# project_vostok__tv_b_gone_extended__v2_0.net
KiCad netlist of a schematic drawn in EAGLE
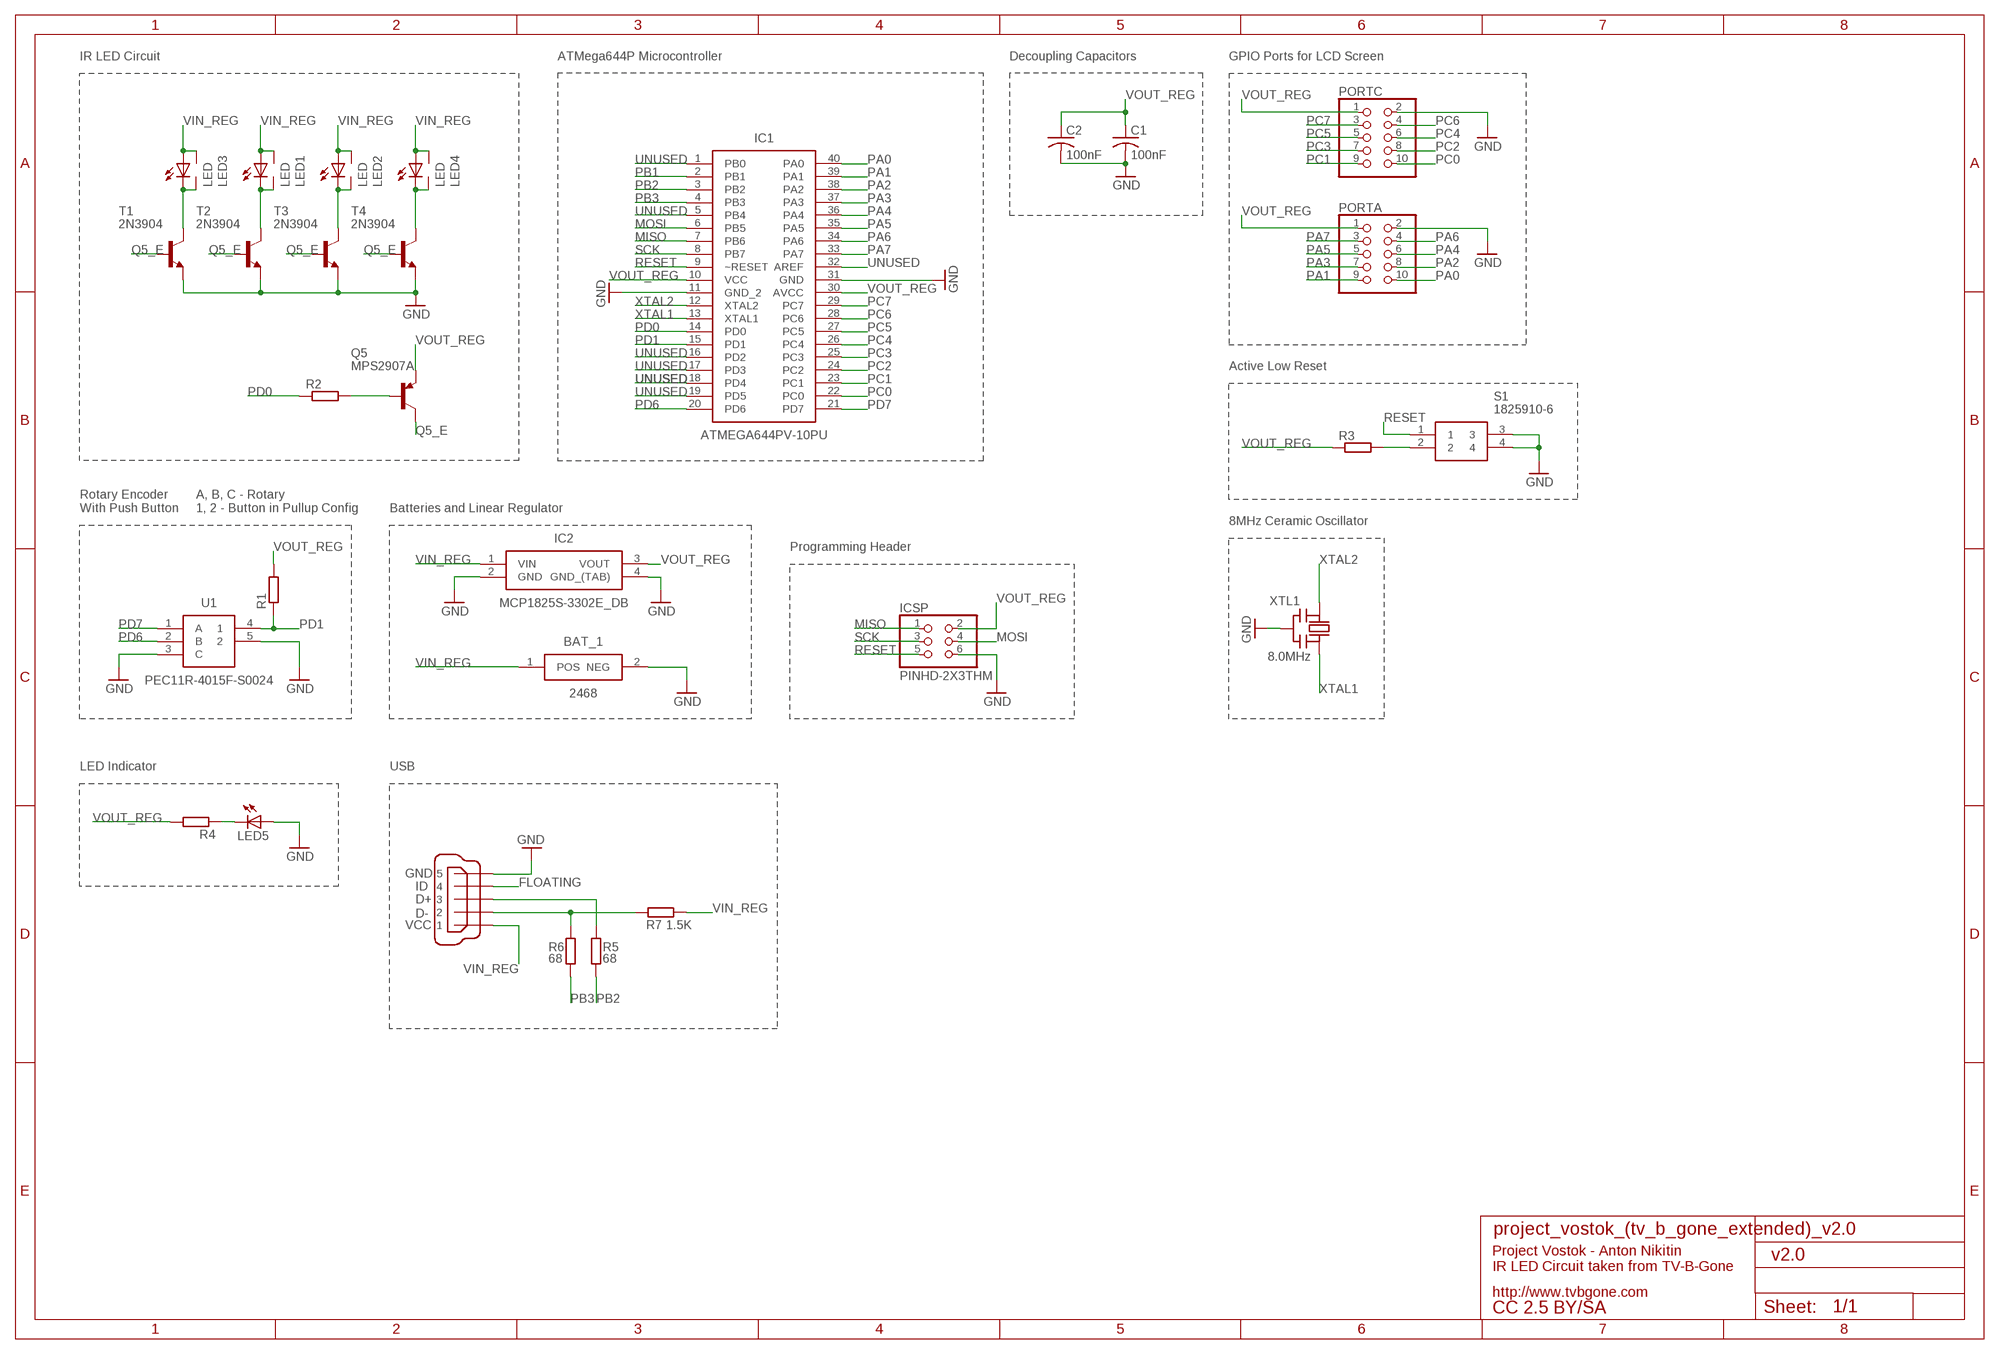
[diagram p0: schematic, sheet 1]

(export (version "E")
  (design (tool "Eeschema 10.0.6"))
  (components
    (comp (ref "BAT_1")
      (value "2468")
      (footprint "eagle-import:2468")
      (fields (field (name "RS_PART_NUMBER") "2794965"))
      (libsource (lib "eagle-import") (part "2468"))
    )
    (comp (ref "C1")
      (value "100nF")
      (footprint "eagle-import:C025-025X050")
      (libsource (lib "eagle-import") (part "C-US025-025X050"))
    )
    (comp (ref "C2")
      (value "100nF")
      (footprint "eagle-import:C025-025X050")
      (libsource (lib "eagle-import") (part "C-US025-025X050"))
    )
    (comp (ref "IC1")
      (value "ATMEGA644PV-10PU")
      (footprint "eagle-import:DIP254P1524X483-40")
      (fields (field (name "RS_PART_NUMBER") "7380491P"))
      (libsource (lib "eagle-import") (part "ATMEGA644PV-10PU"))
    )
    (comp (ref "IC2")
      (value "MCP1825S-3302E_DB")
      (footprint "eagle-import:SOT230P700X180-4N")
      (fields
        (field (name "MANUFACTURER_PART_NUMBER") "MCP1825S-3302E/DB")
        (field (name "RS_PART_NUMBER") "9115520")
      )
      (libsource (lib "eagle-import") (part "MCP1825S-3302E_DB"))
    )
    (comp (ref "ICSP")
      (value "PINHD-2X3THM")
      (footprint "eagle-import:ISP6")
      (libsource (lib "eagle-import") (part "PINHD-2X3THM"))
    )
    (comp (ref "LED1")
      (value "LED")
      (footprint "eagle-import:5MM-SIDE")
      (libsource (lib "eagle-import") (part "tvbgone_LED"))
    )
    (comp (ref "LED2")
      (value "LED")
      (footprint "eagle-import:5MM-SIDE")
      (libsource (lib "eagle-import") (part "tvbgone_LED"))
    )
    (comp (ref "LED3")
      (value "LED")
      (footprint "eagle-import:5MM-SIDE")
      (libsource (lib "eagle-import") (part "tvbgone_LED"))
    )
    (comp (ref "LED4")
      (value "LED")
      (footprint "eagle-import:5MM-SIDE")
      (libsource (lib "eagle-import") (part "tvbgone_LED"))
    )
    (comp (ref "LED5")
      (value "LED5MM")
      (footprint "eagle-import:LED5MM")
      (libsource (lib "eagle-import") (part "LED5MM"))
    )
    (comp (ref "PORTA")
      (value "PINHD-2X5")
      (footprint "eagle-import:2X05")
      (libsource (lib "eagle-import") (part "PINHD-2X5"))
    )
    (comp (ref "PORTC")
      (value "PINHD-2X5")
      (footprint "eagle-import:2X05")
      (libsource (lib "eagle-import") (part "PINHD-2X5"))
    )
    (comp (ref "Q5")
      (value "MPS2907A")
      (footprint "eagle-import:TO92-CBE")
      (libsource (lib "eagle-import") (part "MPS2907A"))
    )
    (comp (ref "R1")
      (value "R-EU_0204/7")
      (footprint "eagle-import:0204_7")
      (libsource (lib "eagle-import") (part "R-EU_0204/7"))
    )
    (comp (ref "R2")
      (value "R-EU_0204/7")
      (footprint "eagle-import:0204_7")
      (libsource (lib "eagle-import") (part "R-EU_0204/7"))
    )
    (comp (ref "R3")
      (value "R-EU_0204/7")
      (footprint "eagle-import:0204_7")
      (libsource (lib "eagle-import") (part "R-EU_0204/7"))
    )
    (comp (ref "R4")
      (value "R-EU_0204/7")
      (footprint "eagle-import:0204_7")
      (libsource (lib "eagle-import") (part "R-EU_0204/7"))
    )
    (comp (ref "R5")
      (value "68")
      (footprint "eagle-import:0204_7")
      (libsource (lib "eagle-import") (part "R-EU_0204/7"))
    )
    (comp (ref "R6")
      (value "68")
      (footprint "eagle-import:0204_7")
      (libsource (lib "eagle-import") (part "R-EU_0204/7"))
    )
    (comp (ref "R7")
      (value "1.5K")
      (footprint "eagle-import:0204_7")
      (libsource (lib "eagle-import") (part "R-EU_0204/7"))
    )
    (comp (ref "S1")
      (value "1825910-6")
      (footprint "eagle-import:1825910-6")
      (fields (field (name "RS_PART_NUMBER") "1613779"))
      (libsource (lib "eagle-import") (part "1825910-6"))
    )
    (comp (ref "T1")
      (value "2N3904")
      (footprint "eagle-import:TO92")
      (libsource (lib "eagle-import") (part "2N3904"))
    )
    (comp (ref "T2")
      (value "2N3904")
      (footprint "eagle-import:TO92")
      (libsource (lib "eagle-import") (part "2N3904"))
    )
    (comp (ref "T3")
      (value "2N3904")
      (footprint "eagle-import:TO92")
      (libsource (lib "eagle-import") (part "2N3904"))
    )
    (comp (ref "T4")
      (value "2N3904")
      (footprint "eagle-import:TO92")
      (libsource (lib "eagle-import") (part "2N3904"))
    )
    (comp (ref "U1")
      (value "PEC11R-4015F-S0024")
      (footprint "eagle-import:PEC12R-4XXXF-SXXXX_1")
      (fields (field (name "RS_PART_NUMBER") "7377739P"))
      (libsource (lib "eagle-import") (part "PEC11R-4015F-S0024"))
    )
    (comp (ref "X1")
      (value "MINI-USB_SHIELD5P2-32005-601")
      (footprint "eagle-import:32005-601")
      (libsource (lib "eagle-import") (part "MINI-USB_SHIELD5P2-32005-601"))
    )
    (comp (ref "XTL1")
      (value "8.0MHz")
      (footprint "eagle-import:CERM_OSC")
      (libsource (lib "eagle-import") (part "CERMOSCILL"))
    )
  )
  (nets
    (net (code "1") (name "/MISO") (class "Default")
      (node (ref "IC1") (pin "7") (pinfunction "PB6_7") (pintype "passive"))
      (node (ref "ICSP") (pin "1") (pinfunction "1_1") (pintype "passive"))
    )
    (net (code "2") (name "/MOSI") (class "Default")
      (node (ref "IC1") (pin "6") (pinfunction "PB5_6") (pintype "passive"))
      (node (ref "ICSP") (pin "4") (pinfunction "4_4") (pintype "passive"))
    )
    (net (code "3") (name "/PA0") (class "Default")
      (node (ref "IC1") (pin "40") (pinfunction "PA0_40") (pintype "passive"))
      (node (ref "PORTA") (pin "10") (pinfunction "10_10") (pintype "passive"))
    )
    (net (code "4") (name "/PA1") (class "Default")
      (node (ref "IC1") (pin "39") (pinfunction "PA1_39") (pintype "passive"))
      (node (ref "PORTA") (pin "9") (pinfunction "9_9") (pintype "passive"))
    )
    (net (code "5") (name "/PA2") (class "Default")
      (node (ref "IC1") (pin "38") (pinfunction "PA2_38") (pintype "passive"))
      (node (ref "PORTA") (pin "8") (pinfunction "8_8") (pintype "passive"))
    )
    (net (code "6") (name "/PA3") (class "Default")
      (node (ref "IC1") (pin "37") (pinfunction "PA3_37") (pintype "passive"))
      (node (ref "PORTA") (pin "7") (pinfunction "7_7") (pintype "passive"))
    )
    (net (code "7") (name "/PA4") (class "Default")
      (node (ref "IC1") (pin "36") (pinfunction "PA4_36") (pintype "passive"))
      (node (ref "PORTA") (pin "6") (pinfunction "6_6") (pintype "passive"))
    )
    (net (code "8") (name "/PA5") (class "Default")
      (node (ref "IC1") (pin "35") (pinfunction "PA5_35") (pintype "passive"))
      (node (ref "PORTA") (pin "5") (pinfunction "5_5") (pintype "passive"))
    )
    (net (code "9") (name "/PA6") (class "Default")
      (node (ref "IC1") (pin "34") (pinfunction "PA6_34") (pintype "passive"))
      (node (ref "PORTA") (pin "4") (pinfunction "4_4") (pintype "passive"))
    )
    (net (code "10") (name "/PA7") (class "Default")
      (node (ref "IC1") (pin "33") (pinfunction "PA7_33") (pintype "passive"))
      (node (ref "PORTA") (pin "3") (pinfunction "3_3") (pintype "passive"))
    )
    (net (code "11") (name "/PB2") (class "Default")
      (node (ref "IC1") (pin "3") (pinfunction "PB2_3") (pintype "passive"))
      (node (ref "R5") (pin "2") (pinfunction "2_2") (pintype "passive"))
    )
    (net (code "12") (name "/PB3") (class "Default")
      (node (ref "IC1") (pin "4") (pinfunction "PB3_4") (pintype "passive"))
      (node (ref "R6") (pin "2") (pinfunction "2_2") (pintype "passive"))
    )
    (net (code "13") (name "/PC0") (class "Default")
      (node (ref "IC1") (pin "22") (pinfunction "PC0_22") (pintype "passive"))
      (node (ref "PORTC") (pin "10") (pinfunction "10_10") (pintype "passive"))
    )
    (net (code "14") (name "/PC1") (class "Default")
      (node (ref "IC1") (pin "23") (pinfunction "PC1_23") (pintype "passive"))
      (node (ref "PORTC") (pin "9") (pinfunction "9_9") (pintype "passive"))
    )
    (net (code "15") (name "/PC2") (class "Default")
      (node (ref "IC1") (pin "24") (pinfunction "PC2_24") (pintype "passive"))
      (node (ref "PORTC") (pin "8") (pinfunction "8_8") (pintype "passive"))
    )
    (net (code "16") (name "/PC3") (class "Default")
      (node (ref "IC1") (pin "25") (pinfunction "PC3_25") (pintype "passive"))
      (node (ref "PORTC") (pin "7") (pinfunction "7_7") (pintype "passive"))
    )
    (net (code "17") (name "/PC4") (class "Default")
      (node (ref "IC1") (pin "26") (pinfunction "PC4_26") (pintype "passive"))
      (node (ref "PORTC") (pin "6") (pinfunction "6_6") (pintype "passive"))
    )
    (net (code "18") (name "/PC5") (class "Default")
      (node (ref "IC1") (pin "27") (pinfunction "PC5_27") (pintype "passive"))
      (node (ref "PORTC") (pin "5") (pinfunction "5_5") (pintype "passive"))
    )
    (net (code "19") (name "/PC6") (class "Default")
      (node (ref "IC1") (pin "28") (pinfunction "PC6_28") (pintype "passive"))
      (node (ref "PORTC") (pin "4") (pinfunction "4_4") (pintype "passive"))
    )
    (net (code "20") (name "/PC7") (class "Default")
      (node (ref "IC1") (pin "29") (pinfunction "PC7_29") (pintype "passive"))
      (node (ref "PORTC") (pin "3") (pinfunction "3_3") (pintype "passive"))
    )
    (net (code "21") (name "/PD0") (class "Default")
      (node (ref "IC1") (pin "14") (pinfunction "PD0_14") (pintype "passive"))
      (node (ref "R2") (pin "1") (pinfunction "1_1") (pintype "passive"))
    )
    (net (code "22") (name "/PD1") (class "Default")
      (node (ref "IC1") (pin "15") (pinfunction "PD1_15") (pintype "passive"))
      (node (ref "R1") (pin "1") (pinfunction "1_1") (pintype "passive"))
      (node (ref "U1") (pin "4") (pinfunction "1_4") (pintype "passive"))
    )
    (net (code "23") (name "/PD6") (class "Default")
      (node (ref "IC1") (pin "20") (pinfunction "PD6_20") (pintype "passive"))
      (node (ref "U1") (pin "2") (pinfunction "B_2") (pintype "passive"))
    )
    (net (code "24") (name "/PD7") (class "Default")
      (node (ref "IC1") (pin "21") (pinfunction "PD7_21") (pintype "passive"))
      (node (ref "U1") (pin "1") (pinfunction "A_1") (pintype "passive"))
    )
    (net (code "25") (name "/Q5_E") (class "Default")
      (node (ref "Q5") (pin "C") (pinfunction "C_C") (pintype "passive"))
      (node (ref "T1") (pin "2") (pinfunction "B_2") (pintype "passive"))
      (node (ref "T2") (pin "2") (pinfunction "B_2") (pintype "passive"))
      (node (ref "T3") (pin "2") (pinfunction "B_2") (pintype "passive"))
      (node (ref "T4") (pin "2") (pinfunction "B_2") (pintype "passive"))
    )
    (net (code "26") (name "/RESET") (class "Default")
      (node (ref "IC1") (pin "9") (pinfunction "~{RESET}_9") (pintype "passive"))
      (node (ref "ICSP") (pin "5") (pinfunction "5_5") (pintype "passive"))
      (node (ref "S1") (pin "1") (pinfunction "1_1") (pintype "input"))
    )
    (net (code "27") (name "/SCK") (class "Default")
      (node (ref "IC1") (pin "8") (pinfunction "PB7_8") (pintype "passive"))
      (node (ref "ICSP") (pin "3") (pinfunction "3_3") (pintype "passive"))
    )
    (net (code "28") (name "/VIN_REG") (class "Default")
      (node (ref "BAT_1") (pin "1") (pinfunction "POS_1") (pintype "passive"))
      (node (ref "IC2") (pin "1") (pinfunction "VIN_1") (pintype "input"))
      (node (ref "LED1") (pin "A") (pinfunction "A_A") (pintype "passive"))
      (node (ref "LED1") (pin "A2") (pinfunction "A1_A2") (pintype "passive"))
      (node (ref "LED2") (pin "A") (pinfunction "A_A") (pintype "passive"))
      (node (ref "LED2") (pin "A2") (pinfunction "A1_A2") (pintype "passive"))
      (node (ref "LED3") (pin "A") (pinfunction "A_A") (pintype "passive"))
      (node (ref "LED3") (pin "A2") (pinfunction "A1_A2") (pintype "passive"))
      (node (ref "LED4") (pin "A") (pinfunction "A_A") (pintype "passive"))
      (node (ref "LED4") (pin "A2") (pinfunction "A1_A2") (pintype "passive"))
      (node (ref "R7") (pin "2") (pinfunction "2_2") (pintype "passive"))
      (node (ref "X1") (pin "1") (pinfunction "1_1") (pintype "passive"))
    )
    (net (code "29") (name "/VOUT_REG") (class "Default")
      (node (ref "C1") (pin "1") (pinfunction "1_1") (pintype "passive"))
      (node (ref "C2") (pin "1") (pinfunction "1_1") (pintype "passive"))
      (node (ref "IC1") (pin "10") (pinfunction "VCC_10") (pintype "passive"))
      (node (ref "IC1") (pin "30") (pinfunction "AVCC_30") (pintype "passive"))
      (node (ref "IC2") (pin "3") (pinfunction "VOUT_3") (pintype "output"))
      (node (ref "ICSP") (pin "2") (pinfunction "2_2") (pintype "passive"))
      (node (ref "PORTA") (pin "1") (pinfunction "1_1") (pintype "passive"))
      (node (ref "PORTC") (pin "1") (pinfunction "1_1") (pintype "passive"))
      (node (ref "Q5") (pin "E") (pinfunction "E_E") (pintype "passive"))
      (node (ref "R1") (pin "2") (pinfunction "2_2") (pintype "passive"))
      (node (ref "R3") (pin "1") (pinfunction "1_1") (pintype "passive"))
      (node (ref "R4") (pin "2") (pinfunction "2_2") (pintype "passive"))
    )
    (net (code "30") (name "/XTAL1") (class "Default")
      (node (ref "IC1") (pin "13") (pinfunction "XTAL1_13") (pintype "passive"))
      (node (ref "XTL1") (pin "P$3") (pinfunction "OUT_P$3") (pintype "bidirectional"))
    )
    (net (code "31") (name "/XTAL2") (class "Default")
      (node (ref "IC1") (pin "12") (pinfunction "XTAL2_12") (pintype "passive"))
      (node (ref "XTL1") (pin "P$1") (pinfunction "IN_P$1") (pintype "bidirectional"))
    )
    (net (code "32") (name "GND") (class "Default")
      (node (ref "BAT_1") (pin "2") (pinfunction "NEG_2") (pintype "passive"))
      (node (ref "C1") (pin "2") (pinfunction "2_2") (pintype "passive"))
      (node (ref "C2") (pin "2") (pinfunction "2_2") (pintype "passive"))
      (node (ref "IC1") (pin "11") (pinfunction "GND_2_11") (pintype "passive"))
      (node (ref "IC1") (pin "31") (pinfunction "GND_31") (pintype "passive"))
      (node (ref "IC2") (pin "2") (pinfunction "GND_2") (pintype "power_in"))
      (node (ref "IC2") (pin "4") (pinfunction "GND_(TAB)_4") (pintype "power_in"))
      (node (ref "ICSP") (pin "6") (pinfunction "6_6") (pintype "passive"))
      (node (ref "LED5") (pin "A") (pinfunction "A_A") (pintype "passive"))
      (node (ref "PORTA") (pin "2") (pinfunction "2_2") (pintype "passive"))
      (node (ref "PORTC") (pin "2") (pinfunction "2_2") (pintype "passive"))
      (node (ref "S1") (pin "3") (pinfunction "3_3") (pintype "input"))
      (node (ref "S1") (pin "4") (pinfunction "4_4") (pintype "input"))
      (node (ref "T1") (pin "3") (pinfunction "E_3") (pintype "passive"))
      (node (ref "T2") (pin "3") (pinfunction "E_3") (pintype "passive"))
      (node (ref "T3") (pin "3") (pinfunction "E_3") (pintype "passive"))
      (node (ref "T4") (pin "3") (pinfunction "E_3") (pintype "passive"))
      (node (ref "U1") (pin "3") (pinfunction "C_3") (pintype "passive"))
      (node (ref "U1") (pin "5") (pinfunction "2_5") (pintype "passive"))
      (node (ref "X1") (pin "5") (pinfunction "5_5") (pintype "passive"))
      (node (ref "XTL1") (pin "P$2") (pinfunction "GND_P$2") (pintype "bidirectional"))
    )
    (net (code "33") (name "Net-(LED1-C)") (class "Default")
      (node (ref "LED1") (pin "K") (pinfunction "C_K") (pintype "passive"))
      (node (ref "LED1") (pin "K2") (pinfunction "C1_K2") (pintype "passive"))
      (node (ref "T2") (pin "1") (pinfunction "C_1") (pintype "passive"))
    )
    (net (code "34") (name "Net-(LED2-C)") (class "Default")
      (node (ref "LED2") (pin "K") (pinfunction "C_K") (pintype "passive"))
      (node (ref "LED2") (pin "K2") (pinfunction "C1_K2") (pintype "passive"))
      (node (ref "T3") (pin "1") (pinfunction "C_1") (pintype "passive"))
    )
    (net (code "35") (name "Net-(LED3-C)") (class "Default")
      (node (ref "LED3") (pin "K") (pinfunction "C_K") (pintype "passive"))
      (node (ref "LED3") (pin "K2") (pinfunction "C1_K2") (pintype "passive"))
      (node (ref "T1") (pin "1") (pinfunction "C_1") (pintype "passive"))
    )
    (net (code "36") (name "Net-(LED4-C)") (class "Default")
      (node (ref "LED4") (pin "K") (pinfunction "C_K") (pintype "passive"))
      (node (ref "LED4") (pin "K2") (pinfunction "C1_K2") (pintype "passive"))
      (node (ref "T4") (pin "1") (pinfunction "C_1") (pintype "passive"))
    )
    (net (code "37") (name "Net-(LED5-C)") (class "Default")
      (node (ref "LED5") (pin "K") (pinfunction "C_K") (pintype "passive"))
      (node (ref "R4") (pin "1") (pinfunction "1_1") (pintype "passive"))
    )
    (net (code "38") (name "Net-(Q5-PadB)") (class "Default")
      (node (ref "Q5") (pin "B") (pinfunction "B_B") (pintype "passive"))
      (node (ref "R2") (pin "2") (pinfunction "2_2") (pintype "passive"))
    )
    (net (code "39") (name "Net-(R3-Pad2)") (class "Default")
      (node (ref "R3") (pin "2") (pinfunction "2_2") (pintype "passive"))
      (node (ref "S1") (pin "2") (pinfunction "2_2") (pintype "input"))
    )
    (net (code "40") (name "Net-(R5-Pad1)") (class "Default")
      (node (ref "R5") (pin "1") (pinfunction "1_1") (pintype "passive"))
      (node (ref "X1") (pin "3") (pinfunction "3_3") (pintype "passive"))
    )
    (net (code "41") (name "Net-(R6-Pad1)") (class "Default")
      (node (ref "R6") (pin "1") (pinfunction "1_1") (pintype "passive"))
      (node (ref "R7") (pin "1") (pinfunction "1_1") (pintype "passive"))
      (node (ref "X1") (pin "2") (pinfunction "2_2") (pintype "passive"))
    )
    (net (code "42") (name "unconnected-(IC1-AREF-Pad32)") (class "Default")
      (node (ref "IC1") (pin "32") (pinfunction "AREF_32") (pintype "passive"))
    )
    (net (code "43") (name "unconnected-(IC1-PB0-Pad1)") (class "Default")
      (node (ref "IC1") (pin "1") (pinfunction "PB0_1") (pintype "passive"))
    )
    (net (code "44") (name "unconnected-(IC1-PB1-Pad2)") (class "Default")
      (node (ref "IC1") (pin "2") (pinfunction "PB1_2") (pintype "passive"))
    )
    (net (code "45") (name "unconnected-(IC1-PB4-Pad5)") (class "Default")
      (node (ref "IC1") (pin "5") (pinfunction "PB4_5") (pintype "passive"))
    )
    (net (code "46") (name "unconnected-(IC1-PD2-Pad16)") (class "Default")
      (node (ref "IC1") (pin "16") (pinfunction "PD2_16") (pintype "passive"))
    )
    (net (code "47") (name "unconnected-(IC1-PD3-Pad17)") (class "Default")
      (node (ref "IC1") (pin "17") (pinfunction "PD3_17") (pintype "passive"))
    )
    (net (code "48") (name "unconnected-(IC1-PD4-Pad18)") (class "Default")
      (node (ref "IC1") (pin "18") (pinfunction "PD4_18") (pintype "passive"))
    )
    (net (code "49") (name "unconnected-(IC1-PD5-Pad19)") (class "Default")
      (node (ref "IC1") (pin "19") (pinfunction "PD5_19") (pintype "passive"))
    )
    (net (code "50") (name "unconnected-(X1-Pad4)") (class "Default")
      (node (ref "X1") (pin "4") (pinfunction "4_4") (pintype "passive"))
    )
  )
)
